# LiPo_4S_balancer.net
KiCad netlist of a schematic drawn in Altium Designer
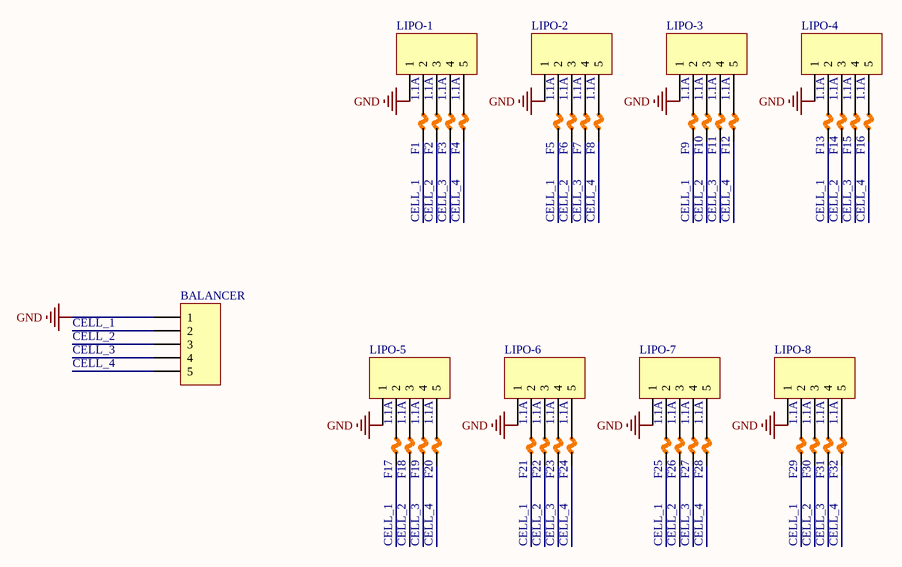
[diagram p0: LiPo_4S_balancer.SchDoc]

(export (version "E")
  (design (tool "Eeschema 10.0.6"))
  (components
    (comp (ref "BALANCER")
      (value "Header 1X5")
      (footprint "HEADER_2.54MM_F_1x5")
      (description "Header, 5-Pin")
      (fields (field (name "PUBLISHER") "Altium Limited"))
      (libsource (lib "") (part "Header 1X5_1"))
    )
    (comp (ref "F1")
      (value "1.1A")
      (footprint "TH multifuse 5mm")
      (description "multifuse")
      (fields (field (name "PART NUMBER") "TODO"))
      (libsource (lib "Fuse") (part "MULTIFUSE"))
    )
    (comp (ref "F2")
      (value "1.1A")
      (footprint "TH multifuse 5mm")
      (description "multifuse")
      (fields (field (name "PART NUMBER") "TODO"))
      (libsource (lib "Fuse") (part "MULTIFUSE"))
    )
    (comp (ref "F3")
      (value "1.1A")
      (footprint "TH multifuse 5mm")
      (description "multifuse")
      (fields (field (name "PART NUMBER") "TODO"))
      (libsource (lib "Fuse") (part "MULTIFUSE"))
    )
    (comp (ref "F4")
      (value "1.1A")
      (footprint "TH multifuse 5mm")
      (description "multifuse")
      (fields (field (name "PART NUMBER") "TODO"))
      (libsource (lib "Fuse") (part "MULTIFUSE"))
    )
    (comp (ref "F5")
      (value "1.1A")
      (footprint "TH multifuse 5mm")
      (description "multifuse")
      (fields (field (name "PART NUMBER") "TODO"))
      (libsource (lib "Fuse") (part "MULTIFUSE"))
    )
    (comp (ref "F6")
      (value "1.1A")
      (footprint "TH multifuse 5mm")
      (description "multifuse")
      (fields (field (name "PART NUMBER") "TODO"))
      (libsource (lib "Fuse") (part "MULTIFUSE"))
    )
    (comp (ref "F7")
      (value "1.1A")
      (footprint "TH multifuse 5mm")
      (description "multifuse")
      (fields (field (name "PART NUMBER") "TODO"))
      (libsource (lib "Fuse") (part "MULTIFUSE"))
    )
    (comp (ref "F8")
      (value "1.1A")
      (footprint "TH multifuse 5mm")
      (description "multifuse")
      (fields (field (name "PART NUMBER") "TODO"))
      (libsource (lib "Fuse") (part "MULTIFUSE"))
    )
    (comp (ref "F9")
      (value "1.1A")
      (footprint "TH multifuse 5mm")
      (description "multifuse")
      (fields (field (name "PART NUMBER") "TODO"))
      (libsource (lib "Fuse") (part "MULTIFUSE"))
    )
    (comp (ref "F10")
      (value "1.1A")
      (footprint "TH multifuse 5mm")
      (description "multifuse")
      (fields (field (name "PART NUMBER") "TODO"))
      (libsource (lib "Fuse") (part "MULTIFUSE"))
    )
    (comp (ref "F11")
      (value "1.1A")
      (footprint "TH multifuse 5mm")
      (description "multifuse")
      (fields (field (name "PART NUMBER") "TODO"))
      (libsource (lib "Fuse") (part "MULTIFUSE"))
    )
    (comp (ref "F12")
      (value "1.1A")
      (footprint "TH multifuse 5mm")
      (description "multifuse")
      (fields (field (name "PART NUMBER") "TODO"))
      (libsource (lib "Fuse") (part "MULTIFUSE"))
    )
    (comp (ref "F13")
      (value "1.1A")
      (footprint "TH multifuse 5mm")
      (description "multifuse")
      (fields (field (name "PART NUMBER") "TODO"))
      (libsource (lib "Fuse") (part "MULTIFUSE"))
    )
    (comp (ref "F14")
      (value "1.1A")
      (footprint "TH multifuse 5mm")
      (description "multifuse")
      (fields (field (name "PART NUMBER") "TODO"))
      (libsource (lib "Fuse") (part "MULTIFUSE"))
    )
    (comp (ref "F15")
      (value "1.1A")
      (footprint "TH multifuse 5mm")
      (description "multifuse")
      (fields (field (name "PART NUMBER") "TODO"))
      (libsource (lib "Fuse") (part "MULTIFUSE"))
    )
    (comp (ref "F16")
      (value "1.1A")
      (footprint "TH multifuse 5mm")
      (description "multifuse")
      (fields (field (name "PART NUMBER") "TODO"))
      (libsource (lib "Fuse") (part "MULTIFUSE"))
    )
    (comp (ref "F17")
      (value "1.1A")
      (footprint "TH multifuse 5mm")
      (description "multifuse")
      (fields (field (name "PART NUMBER") "TODO"))
      (libsource (lib "Fuse") (part "MULTIFUSE"))
    )
    (comp (ref "F18")
      (value "1.1A")
      (footprint "TH multifuse 5mm")
      (description "multifuse")
      (fields (field (name "PART NUMBER") "TODO"))
      (libsource (lib "Fuse") (part "MULTIFUSE"))
    )
    (comp (ref "F19")
      (value "1.1A")
      (footprint "TH multifuse 5mm")
      (description "multifuse")
      (fields (field (name "PART NUMBER") "TODO"))
      (libsource (lib "Fuse") (part "MULTIFUSE"))
    )
    (comp (ref "F20")
      (value "1.1A")
      (footprint "TH multifuse 5mm")
      (description "multifuse")
      (fields (field (name "PART NUMBER") "TODO"))
      (libsource (lib "Fuse") (part "MULTIFUSE"))
    )
    (comp (ref "F21")
      (value "1.1A")
      (footprint "TH multifuse 5mm")
      (description "multifuse")
      (fields (field (name "PART NUMBER") "TODO"))
      (libsource (lib "Fuse") (part "MULTIFUSE"))
    )
    (comp (ref "F22")
      (value "1.1A")
      (footprint "TH multifuse 5mm")
      (description "multifuse")
      (fields (field (name "PART NUMBER") "TODO"))
      (libsource (lib "Fuse") (part "MULTIFUSE"))
    )
    (comp (ref "F23")
      (value "1.1A")
      (footprint "TH multifuse 5mm")
      (description "multifuse")
      (fields (field (name "PART NUMBER") "TODO"))
      (libsource (lib "Fuse") (part "MULTIFUSE"))
    )
    (comp (ref "F24")
      (value "1.1A")
      (footprint "TH multifuse 5mm")
      (description "multifuse")
      (fields (field (name "PART NUMBER") "TODO"))
      (libsource (lib "Fuse") (part "MULTIFUSE"))
    )
    (comp (ref "F25")
      (value "1.1A")
      (footprint "TH multifuse 5mm")
      (description "multifuse")
      (fields (field (name "PART NUMBER") "TODO"))
      (libsource (lib "Fuse") (part "MULTIFUSE"))
    )
    (comp (ref "F26")
      (value "1.1A")
      (footprint "TH multifuse 5mm")
      (description "multifuse")
      (fields (field (name "PART NUMBER") "TODO"))
      (libsource (lib "Fuse") (part "MULTIFUSE"))
    )
    (comp (ref "F27")
      (value "1.1A")
      (footprint "TH multifuse 5mm")
      (description "multifuse")
      (fields (field (name "PART NUMBER") "TODO"))
      (libsource (lib "Fuse") (part "MULTIFUSE"))
    )
    (comp (ref "F28")
      (value "1.1A")
      (footprint "TH multifuse 5mm")
      (description "multifuse")
      (fields (field (name "PART NUMBER") "TODO"))
      (libsource (lib "Fuse") (part "MULTIFUSE"))
    )
    (comp (ref "F29")
      (value "1.1A")
      (footprint "TH multifuse 5mm")
      (description "multifuse")
      (fields (field (name "PART NUMBER") "TODO"))
      (libsource (lib "Fuse") (part "MULTIFUSE"))
    )
    (comp (ref "F30")
      (value "1.1A")
      (footprint "TH multifuse 5mm")
      (description "multifuse")
      (fields (field (name "PART NUMBER") "TODO"))
      (libsource (lib "Fuse") (part "MULTIFUSE"))
    )
    (comp (ref "F31")
      (value "1.1A")
      (footprint "TH multifuse 5mm")
      (description "multifuse")
      (fields (field (name "PART NUMBER") "TODO"))
      (libsource (lib "Fuse") (part "MULTIFUSE"))
    )
    (comp (ref "F32")
      (value "1.1A")
      (footprint "TH multifuse 5mm")
      (description "multifuse")
      (fields (field (name "PART NUMBER") "TODO"))
      (libsource (lib "Fuse") (part "MULTIFUSE"))
    )
    (comp (ref "LIPO-1")
      (value "Header 1X5")
      (footprint "HEADER_2.54MM_F_1x5")
      (description "Header, 5-Pin")
      (fields (field (name "PUBLISHER") "Altium Limited"))
      (libsource (lib "Header") (part "Header 1X5"))
    )
    (comp (ref "LIPO-2")
      (value "Header 1X5")
      (footprint "HEADER_2.54MM_F_1x5")
      (description "Header, 5-Pin")
      (fields (field (name "PUBLISHER") "Altium Limited"))
      (libsource (lib "Header") (part "Header 1X5"))
    )
    (comp (ref "LIPO-3")
      (value "Header 1X5")
      (footprint "HEADER_2.54MM_F_1x5")
      (description "Header, 5-Pin")
      (fields (field (name "PUBLISHER") "Altium Limited"))
      (libsource (lib "Header") (part "Header 1X5"))
    )
    (comp (ref "LIPO-4")
      (value "Header 1X5")
      (footprint "HEADER_2.54MM_F_1x5")
      (description "Header, 5-Pin")
      (fields (field (name "PUBLISHER") "Altium Limited"))
      (libsource (lib "Header") (part "Header 1X5"))
    )
    (comp (ref "LIPO-5")
      (value "Header 1X5")
      (footprint "HEADER_2.54MM_F_1x5")
      (description "Header, 5-Pin")
      (fields (field (name "PUBLISHER") "Altium Limited"))
      (libsource (lib "Header") (part "Header 1X5"))
    )
    (comp (ref "LIPO-6")
      (value "Header 1X5")
      (footprint "HEADER_2.54MM_F_1x5")
      (description "Header, 5-Pin")
      (fields (field (name "PUBLISHER") "Altium Limited"))
      (libsource (lib "Header") (part "Header 1X5"))
    )
    (comp (ref "LIPO-7")
      (value "Header 1X5")
      (footprint "HEADER_2.54MM_F_1x5")
      (description "Header, 5-Pin")
      (fields (field (name "PUBLISHER") "Altium Limited"))
      (libsource (lib "Header") (part "Header 1X5"))
    )
    (comp (ref "LIPO-8")
      (value "Header 1X5")
      (footprint "HEADER_2.54MM_F_1x5")
      (description "Header, 5-Pin")
      (fields (field (name "PUBLISHER") "Altium Limited"))
      (libsource (lib "Header") (part "Header 1X5"))
    )
  )
  (nets
    (net (code "1") (name "/CELL_1") (class "Default")
      (node (ref "BALANCER") (pin "2") (pinfunction "2_2") (pintype "passive"))
      (node (ref "F1") (pin "1") (pinfunction "1_1") (pintype "passive"))
      (node (ref "F13") (pin "1") (pinfunction "1_1") (pintype "passive"))
      (node (ref "F17") (pin "1") (pinfunction "1_1") (pintype "passive"))
      (node (ref "F21") (pin "1") (pinfunction "1_1") (pintype "passive"))
      (node (ref "F25") (pin "1") (pinfunction "1_1") (pintype "passive"))
      (node (ref "F29") (pin "1") (pinfunction "1_1") (pintype "passive"))
      (node (ref "F5") (pin "1") (pinfunction "1_1") (pintype "passive"))
      (node (ref "F9") (pin "1") (pinfunction "1_1") (pintype "passive"))
    )
    (net (code "2") (name "/CELL_2") (class "Default")
      (node (ref "BALANCER") (pin "3") (pinfunction "3_3") (pintype "passive"))
      (node (ref "F10") (pin "1") (pinfunction "1_1") (pintype "passive"))
      (node (ref "F14") (pin "1") (pinfunction "1_1") (pintype "passive"))
      (node (ref "F18") (pin "1") (pinfunction "1_1") (pintype "passive"))
      (node (ref "F2") (pin "1") (pinfunction "1_1") (pintype "passive"))
      (node (ref "F22") (pin "1") (pinfunction "1_1") (pintype "passive"))
      (node (ref "F26") (pin "1") (pinfunction "1_1") (pintype "passive"))
      (node (ref "F30") (pin "1") (pinfunction "1_1") (pintype "passive"))
      (node (ref "F6") (pin "1") (pinfunction "1_1") (pintype "passive"))
    )
    (net (code "3") (name "/CELL_3") (class "Default")
      (node (ref "BALANCER") (pin "4") (pinfunction "4_4") (pintype "passive"))
      (node (ref "F11") (pin "1") (pinfunction "1_1") (pintype "passive"))
      (node (ref "F15") (pin "1") (pinfunction "1_1") (pintype "passive"))
      (node (ref "F19") (pin "1") (pinfunction "1_1") (pintype "passive"))
      (node (ref "F23") (pin "1") (pinfunction "1_1") (pintype "passive"))
      (node (ref "F27") (pin "1") (pinfunction "1_1") (pintype "passive"))
      (node (ref "F3") (pin "1") (pinfunction "1_1") (pintype "passive"))
      (node (ref "F31") (pin "1") (pinfunction "1_1") (pintype "passive"))
      (node (ref "F7") (pin "1") (pinfunction "1_1") (pintype "passive"))
    )
    (net (code "4") (name "/CELL_4") (class "Default")
      (node (ref "BALANCER") (pin "5") (pinfunction "5_5") (pintype "passive"))
      (node (ref "F12") (pin "1") (pinfunction "1_1") (pintype "passive"))
      (node (ref "F16") (pin "1") (pinfunction "1_1") (pintype "passive"))
      (node (ref "F20") (pin "1") (pinfunction "1_1") (pintype "passive"))
      (node (ref "F24") (pin "1") (pinfunction "1_1") (pintype "passive"))
      (node (ref "F28") (pin "1") (pinfunction "1_1") (pintype "passive"))
      (node (ref "F32") (pin "1") (pinfunction "1_1") (pintype "passive"))
      (node (ref "F4") (pin "1") (pinfunction "1_1") (pintype "passive"))
      (node (ref "F8") (pin "1") (pinfunction "1_1") (pintype "passive"))
    )
    (net (code "5") (name "GND") (class "Default")
      (node (ref "BALANCER") (pin "1") (pinfunction "1_1") (pintype "passive"))
      (node (ref "LIPO-1") (pin "1") (pinfunction "1_1") (pintype "passive"))
      (node (ref "LIPO-2") (pin "1") (pinfunction "1_1") (pintype "passive"))
      (node (ref "LIPO-3") (pin "1") (pinfunction "1_1") (pintype "passive"))
      (node (ref "LIPO-4") (pin "1") (pinfunction "1_1") (pintype "passive"))
      (node (ref "LIPO-5") (pin "1") (pinfunction "1_1") (pintype "passive"))
      (node (ref "LIPO-6") (pin "1") (pinfunction "1_1") (pintype "passive"))
      (node (ref "LIPO-7") (pin "1") (pinfunction "1_1") (pintype "passive"))
      (node (ref "LIPO-8") (pin "1") (pinfunction "1_1") (pintype "passive"))
    )
    (net (code "6") (name "Net-(F1-Pad2)") (class "Default")
      (node (ref "F1") (pin "2") (pinfunction "2_2") (pintype "passive"))
      (node (ref "LIPO-1") (pin "2") (pinfunction "2_2") (pintype "passive"))
    )
    (net (code "7") (name "Net-(F2-Pad2)") (class "Default")
      (node (ref "F2") (pin "2") (pinfunction "2_2") (pintype "passive"))
      (node (ref "LIPO-1") (pin "3") (pinfunction "3_3") (pintype "passive"))
    )
    (net (code "8") (name "Net-(F3-Pad2)") (class "Default")
      (node (ref "F3") (pin "2") (pinfunction "2_2") (pintype "passive"))
      (node (ref "LIPO-1") (pin "4") (pinfunction "4_4") (pintype "passive"))
    )
    (net (code "9") (name "Net-(F4-Pad2)") (class "Default")
      (node (ref "F4") (pin "2") (pinfunction "2_2") (pintype "passive"))
      (node (ref "LIPO-1") (pin "5") (pinfunction "5_5") (pintype "passive"))
    )
    (net (code "10") (name "Net-(F5-Pad2)") (class "Default")
      (node (ref "F5") (pin "2") (pinfunction "2_2") (pintype "passive"))
      (node (ref "LIPO-2") (pin "2") (pinfunction "2_2") (pintype "passive"))
    )
    (net (code "11") (name "Net-(F6-Pad2)") (class "Default")
      (node (ref "F6") (pin "2") (pinfunction "2_2") (pintype "passive"))
      (node (ref "LIPO-2") (pin "3") (pinfunction "3_3") (pintype "passive"))
    )
    (net (code "12") (name "Net-(F7-Pad2)") (class "Default")
      (node (ref "F7") (pin "2") (pinfunction "2_2") (pintype "passive"))
      (node (ref "LIPO-2") (pin "4") (pinfunction "4_4") (pintype "passive"))
    )
    (net (code "13") (name "Net-(F8-Pad2)") (class "Default")
      (node (ref "F8") (pin "2") (pinfunction "2_2") (pintype "passive"))
      (node (ref "LIPO-2") (pin "5") (pinfunction "5_5") (pintype "passive"))
    )
    (net (code "14") (name "Net-(F9-Pad2)") (class "Default")
      (node (ref "F9") (pin "2") (pinfunction "2_2") (pintype "passive"))
      (node (ref "LIPO-3") (pin "2") (pinfunction "2_2") (pintype "passive"))
    )
    (net (code "15") (name "Net-(F10-Pad2)") (class "Default")
      (node (ref "F10") (pin "2") (pinfunction "2_2") (pintype "passive"))
      (node (ref "LIPO-3") (pin "3") (pinfunction "3_3") (pintype "passive"))
    )
    (net (code "16") (name "Net-(F11-Pad2)") (class "Default")
      (node (ref "F11") (pin "2") (pinfunction "2_2") (pintype "passive"))
      (node (ref "LIPO-3") (pin "4") (pinfunction "4_4") (pintype "passive"))
    )
    (net (code "17") (name "Net-(F12-Pad2)") (class "Default")
      (node (ref "F12") (pin "2") (pinfunction "2_2") (pintype "passive"))
      (node (ref "LIPO-3") (pin "5") (pinfunction "5_5") (pintype "passive"))
    )
    (net (code "18") (name "Net-(F13-Pad2)") (class "Default")
      (node (ref "F13") (pin "2") (pinfunction "2_2") (pintype "passive"))
      (node (ref "LIPO-4") (pin "2") (pinfunction "2_2") (pintype "passive"))
    )
    (net (code "19") (name "Net-(F14-Pad2)") (class "Default")
      (node (ref "F14") (pin "2") (pinfunction "2_2") (pintype "passive"))
      (node (ref "LIPO-4") (pin "3") (pinfunction "3_3") (pintype "passive"))
    )
    (net (code "20") (name "Net-(F15-Pad2)") (class "Default")
      (node (ref "F15") (pin "2") (pinfunction "2_2") (pintype "passive"))
      (node (ref "LIPO-4") (pin "4") (pinfunction "4_4") (pintype "passive"))
    )
    (net (code "21") (name "Net-(F16-Pad2)") (class "Default")
      (node (ref "F16") (pin "2") (pinfunction "2_2") (pintype "passive"))
      (node (ref "LIPO-4") (pin "5") (pinfunction "5_5") (pintype "passive"))
    )
    (net (code "22") (name "Net-(F17-Pad2)") (class "Default")
      (node (ref "F17") (pin "2") (pinfunction "2_2") (pintype "passive"))
      (node (ref "LIPO-5") (pin "2") (pinfunction "2_2") (pintype "passive"))
    )
    (net (code "23") (name "Net-(F18-Pad2)") (class "Default")
      (node (ref "F18") (pin "2") (pinfunction "2_2") (pintype "passive"))
      (node (ref "LIPO-5") (pin "3") (pinfunction "3_3") (pintype "passive"))
    )
    (net (code "24") (name "Net-(F19-Pad2)") (class "Default")
      (node (ref "F19") (pin "2") (pinfunction "2_2") (pintype "passive"))
      (node (ref "LIPO-5") (pin "4") (pinfunction "4_4") (pintype "passive"))
    )
    (net (code "25") (name "Net-(F20-Pad2)") (class "Default")
      (node (ref "F20") (pin "2") (pinfunction "2_2") (pintype "passive"))
      (node (ref "LIPO-5") (pin "5") (pinfunction "5_5") (pintype "passive"))
    )
    (net (code "26") (name "Net-(F21-Pad2)") (class "Default")
      (node (ref "F21") (pin "2") (pinfunction "2_2") (pintype "passive"))
      (node (ref "LIPO-6") (pin "2") (pinfunction "2_2") (pintype "passive"))
    )
    (net (code "27") (name "Net-(F22-Pad2)") (class "Default")
      (node (ref "F22") (pin "2") (pinfunction "2_2") (pintype "passive"))
      (node (ref "LIPO-6") (pin "3") (pinfunction "3_3") (pintype "passive"))
    )
    (net (code "28") (name "Net-(F23-Pad2)") (class "Default")
      (node (ref "F23") (pin "2") (pinfunction "2_2") (pintype "passive"))
      (node (ref "LIPO-6") (pin "4") (pinfunction "4_4") (pintype "passive"))
    )
    (net (code "29") (name "Net-(F24-Pad2)") (class "Default")
      (node (ref "F24") (pin "2") (pinfunction "2_2") (pintype "passive"))
      (node (ref "LIPO-6") (pin "5") (pinfunction "5_5") (pintype "passive"))
    )
    (net (code "30") (name "Net-(F25-Pad2)") (class "Default")
      (node (ref "F25") (pin "2") (pinfunction "2_2") (pintype "passive"))
      (node (ref "LIPO-7") (pin "2") (pinfunction "2_2") (pintype "passive"))
    )
    (net (code "31") (name "Net-(F26-Pad2)") (class "Default")
      (node (ref "F26") (pin "2") (pinfunction "2_2") (pintype "passive"))
      (node (ref "LIPO-7") (pin "3") (pinfunction "3_3") (pintype "passive"))
    )
    (net (code "32") (name "Net-(F27-Pad2)") (class "Default")
      (node (ref "F27") (pin "2") (pinfunction "2_2") (pintype "passive"))
      (node (ref "LIPO-7") (pin "4") (pinfunction "4_4") (pintype "passive"))
    )
    (net (code "33") (name "Net-(F28-Pad2)") (class "Default")
      (node (ref "F28") (pin "2") (pinfunction "2_2") (pintype "passive"))
      (node (ref "LIPO-7") (pin "5") (pinfunction "5_5") (pintype "passive"))
    )
    (net (code "34") (name "Net-(F29-Pad2)") (class "Default")
      (node (ref "F29") (pin "2") (pinfunction "2_2") (pintype "passive"))
      (node (ref "LIPO-8") (pin "2") (pinfunction "2_2") (pintype "passive"))
    )
    (net (code "35") (name "Net-(F30-Pad2)") (class "Default")
      (node (ref "F30") (pin "2") (pinfunction "2_2") (pintype "passive"))
      (node (ref "LIPO-8") (pin "3") (pinfunction "3_3") (pintype "passive"))
    )
    (net (code "36") (name "Net-(F31-Pad2)") (class "Default")
      (node (ref "F31") (pin "2") (pinfunction "2_2") (pintype "passive"))
      (node (ref "LIPO-8") (pin "4") (pinfunction "4_4") (pintype "passive"))
    )
    (net (code "37") (name "Net-(F32-Pad2)") (class "Default")
      (node (ref "F32") (pin "2") (pinfunction "2_2") (pintype "passive"))
      (node (ref "LIPO-8") (pin "5") (pinfunction "5_5") (pintype "passive"))
    )
  )
)
